# h_bridge.net
KiCad netlist of a schematic drawn in EAGLE
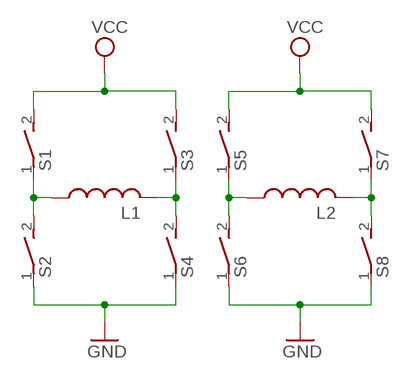
[diagram p0: schematic, sheet 1]

(export (version "E")
  (design (tool "Eeschema 10.0.6"))
  (components
    (comp (ref "L1")
      (value "L-US0204/5")
      (footprint "eagle-import:0204_5")
      (libsource (lib "eagle-import") (part "L-US0204/5"))
    )
    (comp (ref "L2")
      (value "L-US0204/5")
      (footprint "eagle-import:0204_5")
      (libsource (lib "eagle-import") (part "L-US0204/5"))
    )
    (comp (ref "S1")
      (value "DS01E")
      (footprint "eagle-import:DS-01")
      (libsource (lib "eagle-import") (part "DS01E"))
    )
    (comp (ref "S2")
      (value "DS01E")
      (footprint "eagle-import:DS-01")
      (libsource (lib "eagle-import") (part "DS01E"))
    )
    (comp (ref "S3")
      (value "DS01E")
      (footprint "eagle-import:DS-01")
      (libsource (lib "eagle-import") (part "DS01E"))
    )
    (comp (ref "S4")
      (value "DS01E")
      (footprint "eagle-import:DS-01")
      (libsource (lib "eagle-import") (part "DS01E"))
    )
    (comp (ref "S5")
      (value "DS01E")
      (footprint "eagle-import:DS-01")
      (libsource (lib "eagle-import") (part "DS01E"))
    )
    (comp (ref "S6")
      (value "DS01E")
      (footprint "eagle-import:DS-01")
      (libsource (lib "eagle-import") (part "DS01E"))
    )
    (comp (ref "S7")
      (value "DS01E")
      (footprint "eagle-import:DS-01")
      (libsource (lib "eagle-import") (part "DS01E"))
    )
    (comp (ref "S8")
      (value "DS01E")
      (footprint "eagle-import:DS-01")
      (libsource (lib "eagle-import") (part "DS01E"))
    )
  )
  (nets
    (net (code "1") (name "GND") (class "Default")
      (node (ref "S2") (pin "1") (pinfunction "1_1") (pintype "passive"))
      (node (ref "S4") (pin "1") (pinfunction "1_1") (pintype "passive"))
      (node (ref "S6") (pin "1") (pinfunction "1_1") (pintype "passive"))
      (node (ref "S8") (pin "1") (pinfunction "1_1") (pintype "passive"))
    )
    (net (code "2") (name "Net-(L1-Pad1)") (class "Default")
      (node (ref "L1") (pin "1") (pinfunction "1_1") (pintype "passive"))
      (node (ref "S1") (pin "1") (pinfunction "1_1") (pintype "passive"))
      (node (ref "S2") (pin "2") (pinfunction "2_2") (pintype "passive"))
    )
    (net (code "3") (name "Net-(L1-Pad2)") (class "Default")
      (node (ref "L1") (pin "2") (pinfunction "2_2") (pintype "passive"))
      (node (ref "S3") (pin "1") (pinfunction "1_1") (pintype "passive"))
      (node (ref "S4") (pin "2") (pinfunction "2_2") (pintype "passive"))
    )
    (net (code "4") (name "Net-(L2-Pad1)") (class "Default")
      (node (ref "L2") (pin "1") (pinfunction "1_1") (pintype "passive"))
      (node (ref "S5") (pin "1") (pinfunction "1_1") (pintype "passive"))
      (node (ref "S6") (pin "2") (pinfunction "2_2") (pintype "passive"))
    )
    (net (code "5") (name "Net-(L2-Pad2)") (class "Default")
      (node (ref "L2") (pin "2") (pinfunction "2_2") (pintype "passive"))
      (node (ref "S7") (pin "1") (pinfunction "1_1") (pintype "passive"))
      (node (ref "S8") (pin "2") (pinfunction "2_2") (pintype "passive"))
    )
    (net (code "6") (name "VCC") (class "Default")
      (node (ref "S1") (pin "2") (pinfunction "2_2") (pintype "passive"))
      (node (ref "S3") (pin "2") (pinfunction "2_2") (pintype "passive"))
      (node (ref "S5") (pin "2") (pinfunction "2_2") (pintype "passive"))
      (node (ref "S7") (pin "2") (pinfunction "2_2") (pintype "passive"))
    )
  )
)
